# display.net
KiCad netlist of a schematic drawn in EAGLE
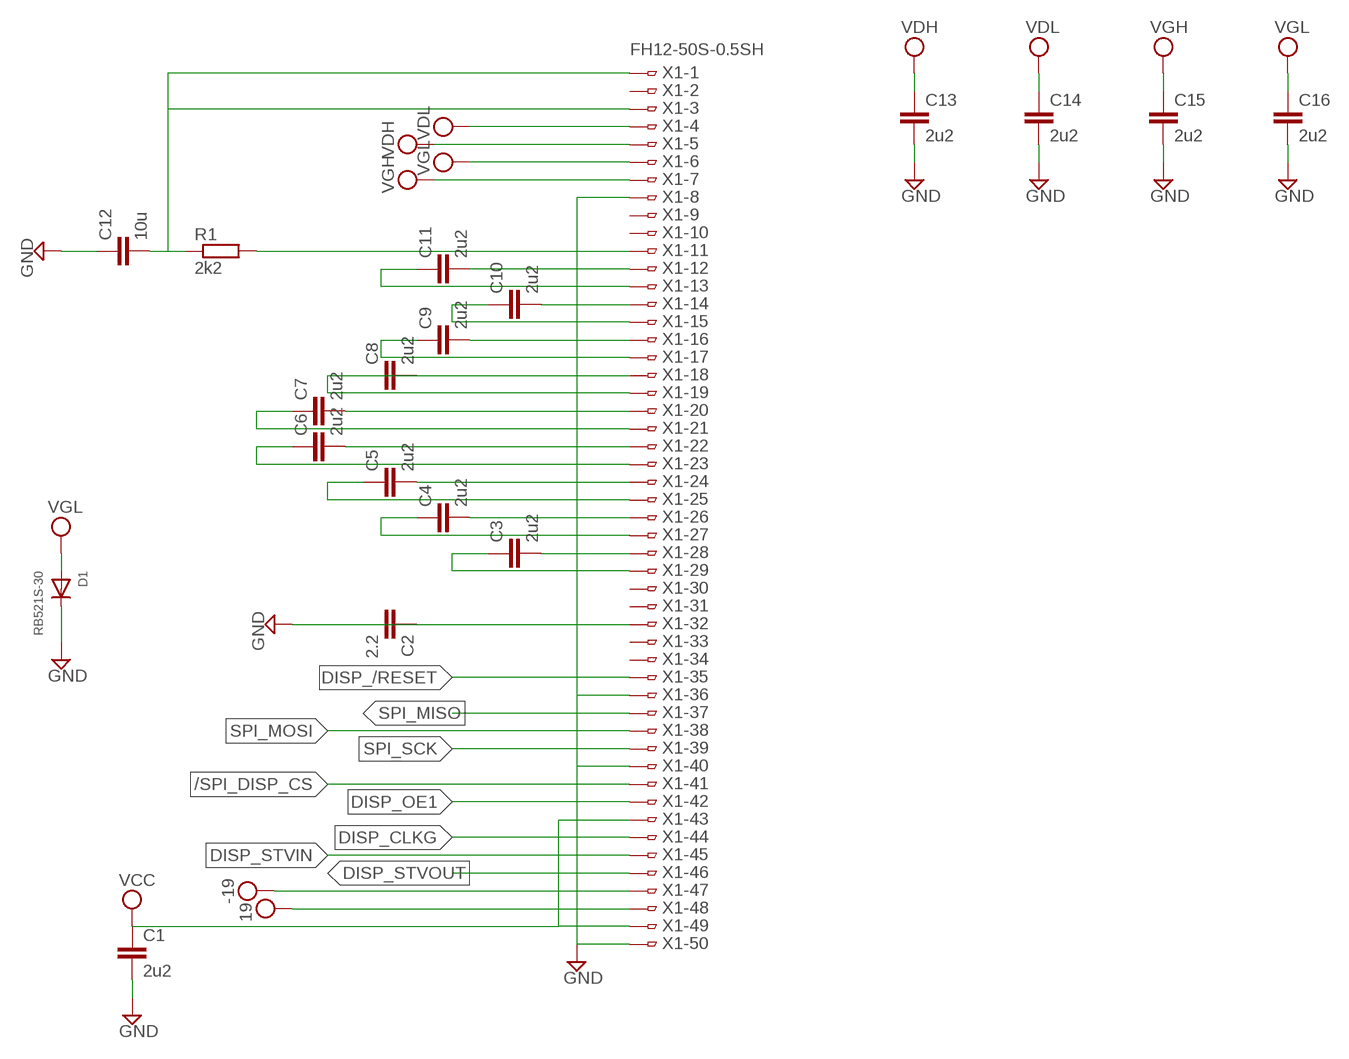
[diagram p0: schematic, sheet 1]

(export (version "E")
  (design (tool "Eeschema 10.0.6"))
  (components
    (comp (ref "C1")
      (value "2u2")
      (footprint "eagle-import:C0603")
      (libsource (lib "eagle-import") (part "C-EUC0603"))
    )
    (comp (ref "C2")
      (value "2.2")
      (footprint "eagle-import:C0603")
      (libsource (lib "eagle-import") (part "C-EUC0603"))
    )
    (comp (ref "C3")
      (value "2u2")
      (footprint "eagle-import:C1608")
      (libsource (lib "eagle-import") (part "C-EUC1608"))
    )
    (comp (ref "C4")
      (value "2u2")
      (footprint "eagle-import:C1608")
      (libsource (lib "eagle-import") (part "C-EUC1608"))
    )
    (comp (ref "C5")
      (value "2u2")
      (footprint "eagle-import:C1608")
      (libsource (lib "eagle-import") (part "C-EUC1608"))
    )
    (comp (ref "C6")
      (value "2u2")
      (footprint "eagle-import:C1608")
      (libsource (lib "eagle-import") (part "C-EUC1608"))
    )
    (comp (ref "C7")
      (value "2u2")
      (footprint "eagle-import:C1608")
      (libsource (lib "eagle-import") (part "C-EUC1608"))
    )
    (comp (ref "C8")
      (value "2u2")
      (footprint "eagle-import:C1608")
      (libsource (lib "eagle-import") (part "C-EUC1608"))
    )
    (comp (ref "C9")
      (value "2u2")
      (footprint "eagle-import:C1608")
      (libsource (lib "eagle-import") (part "C-EUC1608"))
    )
    (comp (ref "C10")
      (value "2u2")
      (footprint "eagle-import:C1608")
      (libsource (lib "eagle-import") (part "C-EUC1608"))
    )
    (comp (ref "C11")
      (value "2u2")
      (footprint "eagle-import:C1608")
      (libsource (lib "eagle-import") (part "C-EUC1608"))
    )
    (comp (ref "C12")
      (value "10u")
      (footprint "eagle-import:C1608")
      (libsource (lib "eagle-import") (part "C-EUC1608"))
    )
    (comp (ref "C13")
      (value "2u2")
      (footprint "eagle-import:C1608")
      (libsource (lib "eagle-import") (part "C-EUC1608"))
    )
    (comp (ref "C14")
      (value "2u2")
      (footprint "eagle-import:C1608")
      (libsource (lib "eagle-import") (part "C-EUC1608"))
    )
    (comp (ref "C15")
      (value "2u2")
      (footprint "eagle-import:C1608")
      (libsource (lib "eagle-import") (part "C-EUC1608"))
    )
    (comp (ref "C16")
      (value "2u2")
      (footprint "eagle-import:C1608")
      (libsource (lib "eagle-import") (part "C-EUC1608"))
    )
    (comp (ref "D1")
      (value "RB521S-30")
      (footprint "eagle-import:SOD-523")
      (libsource (lib "eagle-import") (part "DIODESOD-523"))
    )
    (comp (ref "R1")
      (value "2k2")
      (footprint "eagle-import:R0603")
      (libsource (lib "eagle-import") (part "R-EU_R0603"))
    )
    (comp (ref "X1")
      (value "FH12-50S-0.5SH")
      (footprint "eagle-import:FH12-50S-0.5SH")
      (fields (field (name "MPN") "FH12-50S-0.5SH(55)"))
      (libsource (lib "eagle-import") (part "FH12-50S-0.5SH"))
    )
  )
  (nets
    (net (code "1") (name "-19") (class "Default")
      (node (ref "C16") (pin "1") (pinfunction "1_1") (pintype "passive"))
      (node (ref "D1") (pin "A") (pinfunction "A_A") (pintype "passive"))
      (node (ref "X1") (pin "47") (pinfunction "1_47") (pintype "passive"))
      (node (ref "X1") (pin "6") (pinfunction "1_6") (pintype "passive"))
    )
    (net (code "2") (name "19") (class "Default")
      (node (ref "C15") (pin "1") (pinfunction "1_1") (pintype "passive"))
      (node (ref "X1") (pin "48") (pinfunction "1_48") (pintype "passive"))
      (node (ref "X1") (pin "7") (pinfunction "1_7") (pintype "passive"))
    )
    (net (code "3") (name "DISP_CLKG") (class "Default")
      (node (ref "X1") (pin "44") (pinfunction "1_44") (pintype "passive"))
    )
    (net (code "4") (name "DISP_OE1") (class "Default")
      (node (ref "X1") (pin "42") (pinfunction "1_42") (pintype "passive"))
    )
    (net (code "5") (name "DISP_STVIN") (class "Default")
      (node (ref "X1") (pin "45") (pinfunction "1_45") (pintype "passive"))
    )
    (net (code "6") (name "DISP_STVOUT") (class "Default")
      (node (ref "X1") (pin "46") (pinfunction "1_46") (pintype "passive"))
    )
    (net (code "7") (name "DISP_{slash}RESET") (class "Default")
      (node (ref "X1") (pin "35") (pinfunction "1_35") (pintype "passive"))
    )
    (net (code "8") (name "GND") (class "Default")
      (node (ref "C1") (pin "2") (pinfunction "2_2") (pintype "passive"))
      (node (ref "C12") (pin "1") (pinfunction "1_1") (pintype "passive"))
      (node (ref "C13") (pin "2") (pinfunction "2_2") (pintype "passive"))
      (node (ref "C14") (pin "2") (pinfunction "2_2") (pintype "passive"))
      (node (ref "C15") (pin "2") (pinfunction "2_2") (pintype "passive"))
      (node (ref "C16") (pin "2") (pinfunction "2_2") (pintype "passive"))
      (node (ref "C2") (pin "1") (pinfunction "1_1") (pintype "passive"))
      (node (ref "C2") (pin "2") (pinfunction "2_2") (pintype "passive"))
      (node (ref "D1") (pin "K") (pinfunction "C_K") (pintype "passive"))
      (node (ref "X1") (pin "32") (pinfunction "1_32") (pintype "passive"))
      (node (ref "X1") (pin "36") (pinfunction "1_36") (pintype "passive"))
      (node (ref "X1") (pin "40") (pinfunction "1_40") (pintype "passive"))
      (node (ref "X1") (pin "50") (pinfunction "1_50") (pintype "passive"))
      (node (ref "X1") (pin "8") (pinfunction "1_8") (pintype "passive"))
    )
    (net (code "9") (name "Net-(X1C-1)") (class "Default")
      (node (ref "R1") (pin "2") (pinfunction "2_2") (pintype "passive"))
      (node (ref "X1") (pin "11") (pinfunction "1_11") (pintype "passive"))
    )
    (net (code "10") (name "Net-(X1D-1)") (class "Default")
      (node (ref "C11") (pin "2") (pinfunction "2_2") (pintype "passive"))
      (node (ref "X1") (pin "12") (pinfunction "1_12") (pintype "passive"))
    )
    (net (code "11") (name "Net-(X1E-1)") (class "Default")
      (node (ref "C11") (pin "1") (pinfunction "1_1") (pintype "passive"))
      (node (ref "X1") (pin "13") (pinfunction "1_13") (pintype "passive"))
    )
    (net (code "12") (name "Net-(X1F-1)") (class "Default")
      (node (ref "C10") (pin "2") (pinfunction "2_2") (pintype "passive"))
      (node (ref "X1") (pin "14") (pinfunction "1_14") (pintype "passive"))
    )
    (net (code "13") (name "Net-(X1G-1)") (class "Default")
      (node (ref "C10") (pin "1") (pinfunction "1_1") (pintype "passive"))
      (node (ref "X1") (pin "15") (pinfunction "1_15") (pintype "passive"))
    )
    (net (code "14") (name "Net-(X1H-1)") (class "Default")
      (node (ref "C9") (pin "2") (pinfunction "2_2") (pintype "passive"))
      (node (ref "X1") (pin "16") (pinfunction "1_16") (pintype "passive"))
    )
    (net (code "15") (name "Net-(X1I-1)") (class "Default")
      (node (ref "C9") (pin "1") (pinfunction "1_1") (pintype "passive"))
      (node (ref "X1") (pin "17") (pinfunction "1_17") (pintype "passive"))
    )
    (net (code "16") (name "Net-(X1J-1)") (class "Default")
      (node (ref "C8") (pin "1") (pinfunction "1_1") (pintype "passive"))
      (node (ref "C8") (pin "2") (pinfunction "2_2") (pintype "passive"))
      (node (ref "X1") (pin "18") (pinfunction "1_18") (pintype "passive"))
      (node (ref "X1") (pin "19") (pinfunction "1_19") (pintype "passive"))
    )
    (net (code "17") (name "Net-(X1M-1)") (class "Default")
      (node (ref "C7") (pin "2") (pinfunction "2_2") (pintype "passive"))
      (node (ref "X1") (pin "20") (pinfunction "1_20") (pintype "passive"))
    )
    (net (code "18") (name "Net-(X1N-1)") (class "Default")
      (node (ref "C7") (pin "1") (pinfunction "1_1") (pintype "passive"))
      (node (ref "X1") (pin "21") (pinfunction "1_21") (pintype "passive"))
    )
    (net (code "19") (name "Net-(X1O-1)") (class "Default")
      (node (ref "C6") (pin "2") (pinfunction "2_2") (pintype "passive"))
      (node (ref "X1") (pin "22") (pinfunction "1_22") (pintype "passive"))
    )
    (net (code "20") (name "Net-(X1P-1)") (class "Default")
      (node (ref "C6") (pin "1") (pinfunction "1_1") (pintype "passive"))
      (node (ref "X1") (pin "23") (pinfunction "1_23") (pintype "passive"))
    )
    (net (code "21") (name "Net-(X1Q-1)") (class "Default")
      (node (ref "C5") (pin "2") (pinfunction "2_2") (pintype "passive"))
      (node (ref "X1") (pin "24") (pinfunction "1_24") (pintype "passive"))
    )
    (net (code "22") (name "Net-(X1R-1)") (class "Default")
      (node (ref "C5") (pin "1") (pinfunction "1_1") (pintype "passive"))
      (node (ref "X1") (pin "25") (pinfunction "1_25") (pintype "passive"))
    )
    (net (code "23") (name "Net-(X1S-1)") (class "Default")
      (node (ref "C4") (pin "2") (pinfunction "2_2") (pintype "passive"))
      (node (ref "X1") (pin "26") (pinfunction "1_26") (pintype "passive"))
    )
    (net (code "24") (name "Net-(X1T-1)") (class "Default")
      (node (ref "C4") (pin "1") (pinfunction "1_1") (pintype "passive"))
      (node (ref "X1") (pin "27") (pinfunction "1_27") (pintype "passive"))
    )
    (net (code "25") (name "Net-(X1U-1)") (class "Default")
      (node (ref "C3") (pin "2") (pinfunction "2_2") (pintype "passive"))
      (node (ref "X1") (pin "28") (pinfunction "1_28") (pintype "passive"))
    )
    (net (code "26") (name "Net-(X1V-1)") (class "Default")
      (node (ref "C3") (pin "1") (pinfunction "1_1") (pintype "passive"))
      (node (ref "X1") (pin "29") (pinfunction "1_29") (pintype "passive"))
    )
    (net (code "27") (name "Net-(X1W-1)") (class "Default")
      (node (ref "C12") (pin "2") (pinfunction "2_2") (pintype "passive"))
      (node (ref "R1") (pin "1") (pinfunction "1_1") (pintype "passive"))
      (node (ref "X1") (pin "1") (pinfunction "1_1") (pintype "passive"))
      (node (ref "X1") (pin "3") (pinfunction "1_3") (pintype "passive"))
    )
    (net (code "28") (name "SPI_MISO") (class "Default")
      (node (ref "X1") (pin "37") (pinfunction "1_37") (pintype "passive"))
    )
    (net (code "29") (name "SPI_MOSI") (class "Default")
      (node (ref "X1") (pin "38") (pinfunction "1_38") (pintype "passive"))
    )
    (net (code "30") (name "SPI_SCK") (class "Default")
      (node (ref "X1") (pin "39") (pinfunction "1_39") (pintype "passive"))
    )
    (net (code "31") (name "VCC") (class "Default")
      (node (ref "C1") (pin "1") (pinfunction "1_1") (pintype "passive"))
      (node (ref "X1") (pin "43") (pinfunction "1_43") (pintype "passive"))
      (node (ref "X1") (pin "49") (pinfunction "1_49") (pintype "passive"))
    )
    (net (code "32") (name "VDH") (class "Default")
      (node (ref "C13") (pin "1") (pinfunction "1_1") (pintype "passive"))
      (node (ref "X1") (pin "5") (pinfunction "1_5") (pintype "passive"))
    )
    (net (code "33") (name "VDL") (class "Default")
      (node (ref "C14") (pin "1") (pinfunction "1_1") (pintype "passive"))
      (node (ref "X1") (pin "4") (pinfunction "1_4") (pintype "passive"))
    )
    (net (code "34") (name "unconnected-(X1AA-1-Pad33)") (class "Default")
      (node (ref "X1") (pin "33") (pinfunction "1_33") (pintype "passive"))
    )
    (net (code "35") (name "unconnected-(X1AB-1-Pad34)") (class "Default")
      (node (ref "X1") (pin "34") (pinfunction "1_34") (pintype "passive"))
    )
    (net (code "36") (name "unconnected-(X1AX-1-Pad9)") (class "Default")
      (node (ref "X1") (pin "9") (pinfunction "1_9") (pintype "passive"))
    )
    (net (code "37") (name "unconnected-(X1B-1-Pad10)") (class "Default")
      (node (ref "X1") (pin "10") (pinfunction "1_10") (pintype "passive"))
    )
    (net (code "38") (name "unconnected-(X1L-1-Pad2)") (class "Default")
      (node (ref "X1") (pin "2") (pinfunction "1_2") (pintype "passive"))
    )
    (net (code "39") (name "unconnected-(X1X-1-Pad30)") (class "Default")
      (node (ref "X1") (pin "30") (pinfunction "1_30") (pintype "passive"))
    )
    (net (code "40") (name "unconnected-(X1Y-1-Pad31)") (class "Default")
      (node (ref "X1") (pin "31") (pinfunction "1_31") (pintype "passive"))
    )
    (net (code "41") (name "{slash}SPI_DISP_CS") (class "Default")
      (node (ref "X1") (pin "41") (pinfunction "1_41") (pintype "passive"))
    )
  )
)
